# KSP8_Power_Supply_Board_v48.net
KiCad netlist of a schematic drawn in EAGLE
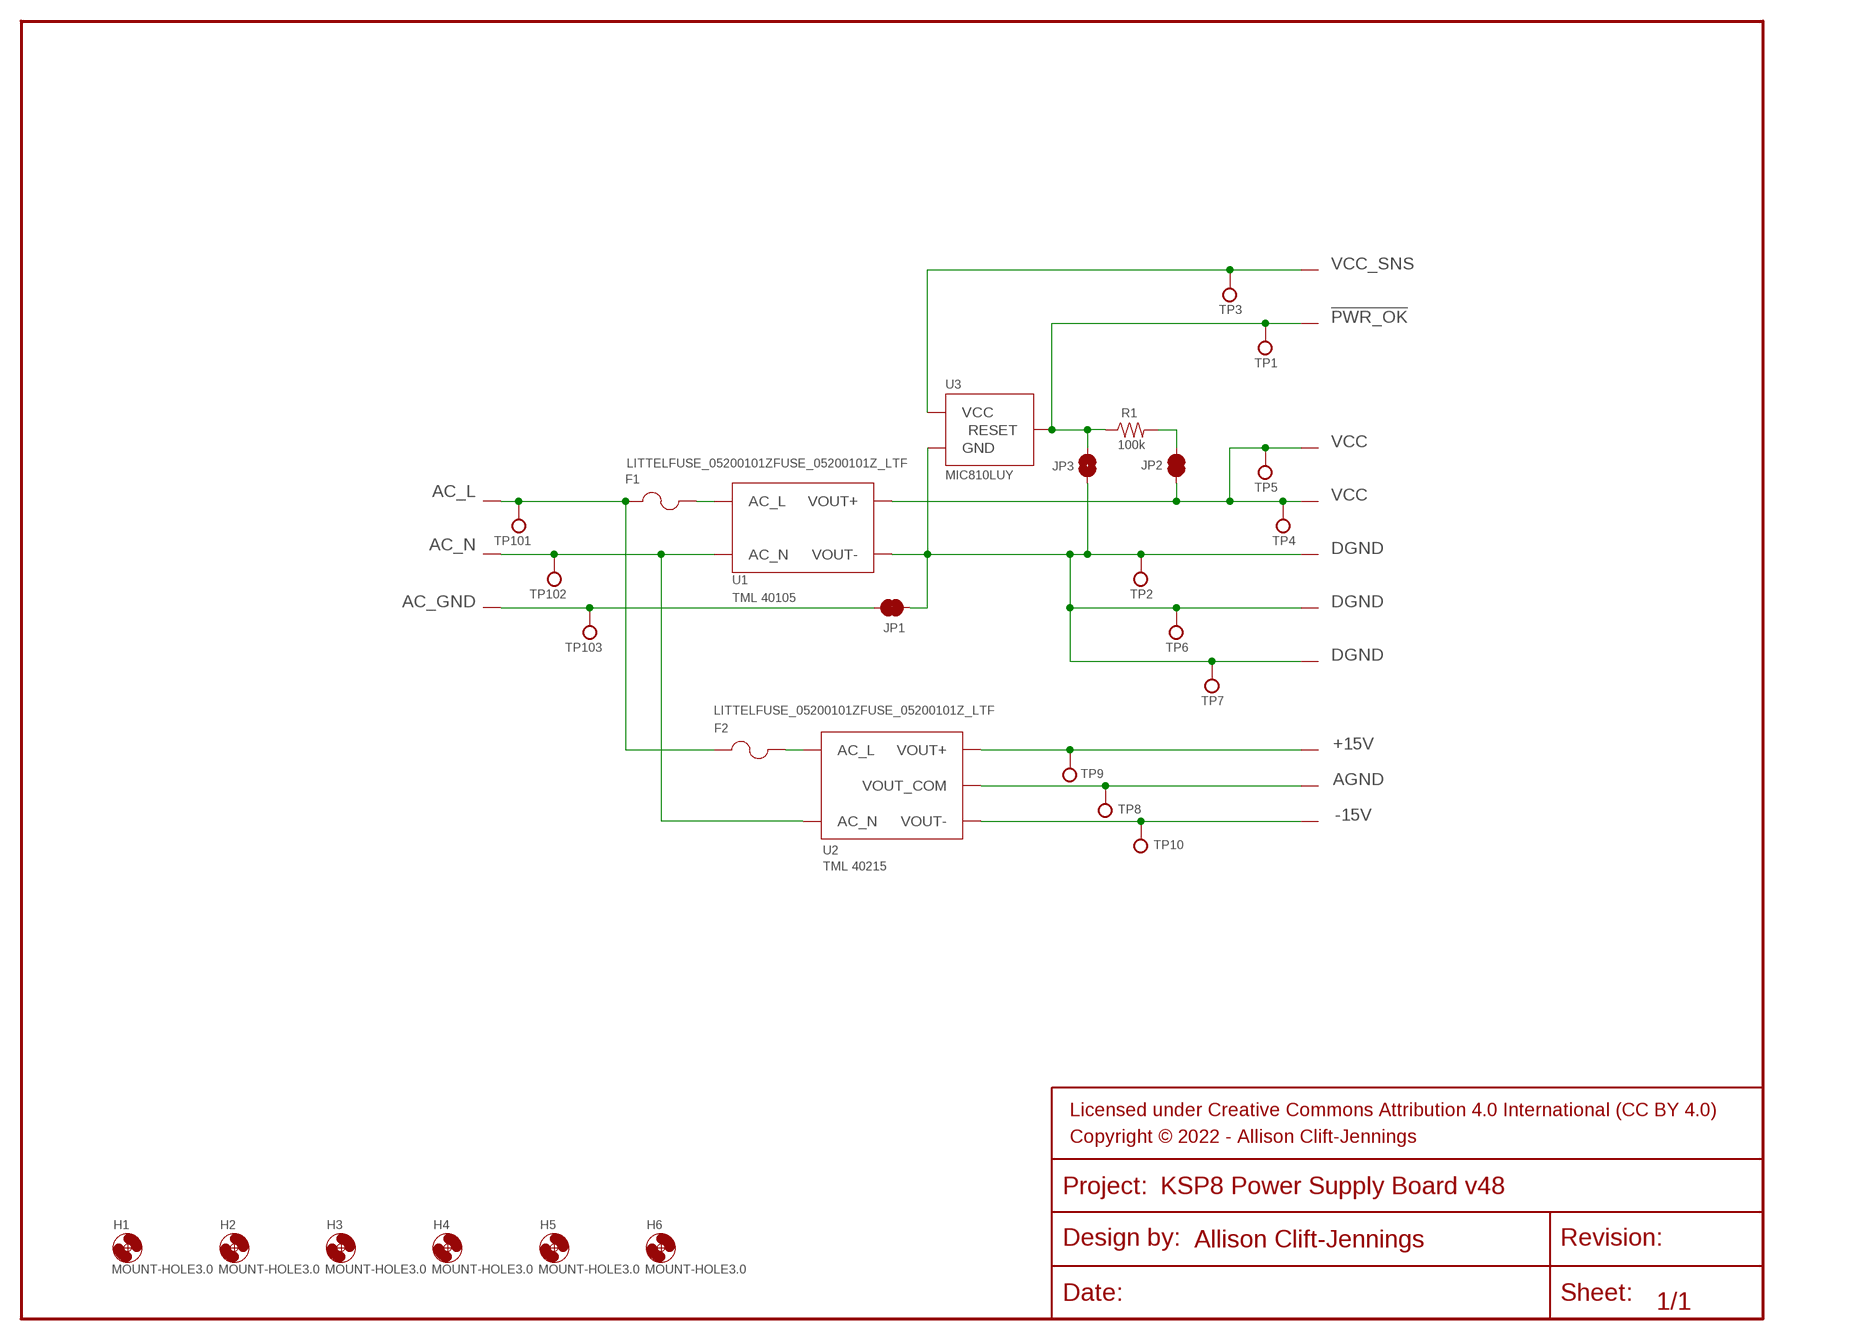
[diagram p0: schematic, sheet 1]

(export (version "E")
  (design (tool "Eeschema 10.0.6"))
  (components
    (comp (ref "AGND")
      (value "PADPAD-070-LOOP")
      (footprint "eagle-import:PAD-067-LOOP")
      (libsource (lib "eagle-import") (part "PAD067-LOOP"))
    )
    (comp (ref "F1")
      (value "LITTELFUSE_05200101ZFUSE_05200101Z_LTF")
      (footprint "eagle-import:LITTELFUSE_05200101Z_LTF")
      (fields
        (field (name "MANUFACTURER_PART_NUMBER") "05200101Z")
        (field (name "COPYRIGHT") "Copyright (C) 2022 Ultra Librarian. All rights reserved.")
      )
      (libsource (lib "eagle-import") (part "LITTELFUSE_05200101ZFUSE_05200101Z_LTF"))
    )
    (comp (ref "F2")
      (value "LITTELFUSE_05200101ZFUSE_05200101Z_LTF")
      (footprint "eagle-import:LITTELFUSE_05200101Z_LTF")
      (fields
        (field (name "MANUFACTURER_PART_NUMBER") "05200101Z")
        (field (name "COPYRIGHT") "Copyright (C) 2022 Ultra Librarian. All rights reserved.")
      )
      (libsource (lib "eagle-import") (part "LITTELFUSE_05200101ZFUSE_05200101Z_LTF"))
    )
    (comp (ref "FRAME1")
      (value "FRAME-LETTER-OS")
      (footprint "eagle-import:CREATIVE_COMMONS")
      (libsource (lib "eagle-import") (part "FRAME-LETTER-OS"))
    )
    (comp (ref "H1")
      (value "MOUNT-HOLE3.0")
      (footprint "eagle-import:3,0")
      (libsource (lib "eagle-import") (part "MOUNT-HOLE3.0"))
    )
    (comp (ref "H2")
      (value "MOUNT-HOLE3.0")
      (footprint "eagle-import:3,0")
      (libsource (lib "eagle-import") (part "MOUNT-HOLE3.0"))
    )
    (comp (ref "H3")
      (value "MOUNT-HOLE3.0")
      (footprint "eagle-import:3,0")
      (libsource (lib "eagle-import") (part "MOUNT-HOLE3.0"))
    )
    (comp (ref "H4")
      (value "MOUNT-HOLE3.0")
      (footprint "eagle-import:3,0")
      (libsource (lib "eagle-import") (part "MOUNT-HOLE3.0"))
    )
    (comp (ref "H5")
      (value "MOUNT-HOLE3.0")
      (footprint "eagle-import:3,0")
      (libsource (lib "eagle-import") (part "MOUNT-HOLE3.0"))
    )
    (comp (ref "H6")
      (value "MOUNT-HOLE3.0")
      (footprint "eagle-import:3,0")
      (libsource (lib "eagle-import") (part "MOUNT-HOLE3.0"))
    )
    (comp (ref "JP1")
      (value "JUMPER-SMT_2_NO_SILK")
      (footprint "eagle-import:SMT-JUMPER_2_NC_TRACE_SILK_HC")
      (libsource (lib "eagle-import") (part "JUMPER-SMT_2_NC_TRACEHC"))
    )
    (comp (ref "JP2")
      (value "JUMPER-SMT_2_NC_TRACE_SILK")
      (footprint "eagle-import:SMT-JUMPER_2_NC_TRACE_SILK")
      (libsource (lib "eagle-import") (part "JUMPER-SMT_2_NC_TRACE_SILK"))
    )
    (comp (ref "JP3")
      (value "JUMPER-SMT_2_NO_SILK")
      (footprint "eagle-import:SMT-JUMPER_2_NO_SILK")
      (libsource (lib "eagle-import") (part "JUMPER-SMT_2_NO_SILK"))
    )
    (comp (ref "R1")
      (value "100k")
      (footprint "eagle-import:1206")
      (libsource (lib "eagle-import") (part "RESISTOR1206"))
    )
    (comp (ref "TP1")
      (value "TESTPOINT")
      (footprint "eagle-import:PAD-100-RND")
      (libsource (lib "eagle-import") (part "TESTPOINT"))
    )
    (comp (ref "TP2")
      (value "TESTPOINT")
      (footprint "eagle-import:PAD-100-RND")
      (libsource (lib "eagle-import") (part "TESTPOINT"))
    )
    (comp (ref "TP3")
      (value "TESTPOINT")
      (footprint "eagle-import:PAD-100-RND")
      (libsource (lib "eagle-import") (part "TESTPOINT"))
    )
    (comp (ref "TP4")
      (value "TESTPOINT")
      (footprint "eagle-import:PAD-100-RND")
      (libsource (lib "eagle-import") (part "TESTPOINT"))
    )
    (comp (ref "TP5")
      (value "TESTPOINT")
      (footprint "eagle-import:PAD-100-RND")
      (libsource (lib "eagle-import") (part "TESTPOINT"))
    )
    (comp (ref "TP6")
      (value "TESTPOINT")
      (footprint "eagle-import:PAD-100-RND")
      (libsource (lib "eagle-import") (part "TESTPOINT"))
    )
    (comp (ref "TP7")
      (value "TESTPOINT")
      (footprint "eagle-import:PAD-100-RND")
      (libsource (lib "eagle-import") (part "TESTPOINT"))
    )
    (comp (ref "TP8")
      (value "TESTPOINT")
      (footprint "eagle-import:PAD-100-RND")
      (libsource (lib "eagle-import") (part "TESTPOINT"))
    )
    (comp (ref "TP9")
      (value "TESTPOINT")
      (footprint "eagle-import:PAD-100-RND")
      (libsource (lib "eagle-import") (part "TESTPOINT"))
    )
    (comp (ref "TP10")
      (value "TESTPOINT")
      (footprint "eagle-import:PAD-100-RND")
      (libsource (lib "eagle-import") (part "TESTPOINT"))
    )
    (comp (ref "TP101")
      (value "TESTPOINT")
      (footprint "eagle-import:PAD-100-RND")
      (libsource (lib "eagle-import") (part "TESTPOINT"))
    )
    (comp (ref "TP102")
      (value "TESTPOINT")
      (footprint "eagle-import:PAD-100-RND")
      (libsource (lib "eagle-import") (part "TESTPOINT"))
    )
    (comp (ref "TP103")
      (value "TESTPOINT")
      (footprint "eagle-import:PAD-100-RND")
      (libsource (lib "eagle-import") (part "TESTPOINT"))
    )
    (comp (ref "U$4")
      (value "PADPAD-070-LOOP")
      (footprint "eagle-import:PAD-067-LOOP")
      (libsource (lib "eagle-import") (part "PAD067-LOOP"))
    )
    (comp (ref "U$5")
      (value "PADPAD-070-LOOP")
      (footprint "eagle-import:PAD-067-LOOP")
      (libsource (lib "eagle-import") (part "PAD067-LOOP"))
    )
    (comp (ref "U$6")
      (value "PADPAD-070-LOOP")
      (footprint "eagle-import:PAD-067-LOOP")
      (libsource (lib "eagle-import") (part "PAD067-LOOP"))
    )
    (comp (ref "U$7")
      (value "PADPAD-070-LOOP")
      (footprint "eagle-import:PAD-067-LOOP")
      (libsource (lib "eagle-import") (part "PAD067-LOOP"))
    )
    (comp (ref "U$8")
      (value "PADPAD-070-LOOP")
      (footprint "eagle-import:PAD-067-LOOP")
      (libsource (lib "eagle-import") (part "PAD067-LOOP"))
    )
    (comp (ref "U$9")
      (value "PADPAD-070-LOOP")
      (footprint "eagle-import:PAD-067-LOOP")
      (libsource (lib "eagle-import") (part "PAD067-LOOP"))
    )
    (comp (ref "U$10")
      (value "PADPAD-070-LOOP")
      (footprint "eagle-import:PAD-067-LOOP")
      (libsource (lib "eagle-import") (part "PAD067-LOOP"))
    )
    (comp (ref "U$11")
      (value "PADPAD-070-LOOP")
      (footprint "eagle-import:PAD-067-LOOP")
      (libsource (lib "eagle-import") (part "PAD067-LOOP"))
    )
    (comp (ref "U$12")
      (value "PADPAD-070-LOOP")
      (footprint "eagle-import:PAD-067-LOOP")
      (libsource (lib "eagle-import") (part "PAD067-LOOP"))
    )
    (comp (ref "U$13")
      (value "PADPAD-070-LOOP")
      (footprint "eagle-import:PAD-067-LOOP")
      (libsource (lib "eagle-import") (part "PAD067-LOOP"))
    )
    (comp (ref "U$14")
      (value "PADPAD-070-LOOP")
      (footprint "eagle-import:PAD-067-LOOP")
      (libsource (lib "eagle-import") (part "PAD067-LOOP"))
    )
    (comp (ref "U$15")
      (value "PADPAD-070-LOOP")
      (footprint "eagle-import:PAD-067-LOOP")
      (libsource (lib "eagle-import") (part "PAD067-LOOP"))
    )
    (comp (ref "U1")
      (value "TML 40105")
      (footprint "eagle-import:TRACO_TML")
      (libsource (lib "eagle-import") (part "TRACO_TML_40105"))
    )
    (comp (ref "U2")
      (value "TML 40215")
      (footprint "eagle-import:TRACO_TML")
      (libsource (lib "eagle-import") (part "TRACO_TML_40215"))
    )
    (comp (ref "U3")
      (value "MIC810LUY")
      (footprint "eagle-import:SOT23")
      (libsource (lib "eagle-import") (part "MIC810"))
    )
  )
  (nets
    (net (code "1") (name "/+15V") (class "Default")
      (node (ref "TP9") (pin "P$1") (pinfunction "P$1_P$1") (pintype "bidirectional"))
      (node (ref "U$6") (pin "P$1") (pinfunction "P$1_P$1") (pintype "bidirectional"))
      (node (ref "U2") (pin "P$4") (pinfunction "VOUT+_P$4") (pintype "power_in"))
    )
    (net (code "2") (name "/-15V") (class "Default")
      (node (ref "TP10") (pin "P$1") (pinfunction "P$1_P$1") (pintype "bidirectional"))
      (node (ref "U$7") (pin "P$1") (pinfunction "P$1_P$1") (pintype "bidirectional"))
      (node (ref "U2") (pin "P$8") (pinfunction "VOUT-_P$8") (pintype "power_in"))
    )
    (net (code "3") (name "/AC_GND") (class "Default")
      (node (ref "JP1") (pin "1") (pinfunction "1_1") (pintype "passive"))
      (node (ref "TP103") (pin "P$1") (pinfunction "P$1_P$1") (pintype "bidirectional"))
      (node (ref "U$11") (pin "P$1") (pinfunction "P$1_P$1") (pintype "bidirectional"))
    )
    (net (code "4") (name "/AC_L") (class "Default")
      (node (ref "F1") (pin "1") (pinfunction "1_1") (pintype "passive"))
      (node (ref "F2") (pin "1") (pinfunction "1_1") (pintype "passive"))
      (node (ref "TP101") (pin "P$1") (pinfunction "P$1_P$1") (pintype "bidirectional"))
      (node (ref "U$4") (pin "P$1") (pinfunction "P$1_P$1") (pintype "bidirectional"))
    )
    (net (code "5") (name "/AC_N") (class "Default")
      (node (ref "TP102") (pin "P$1") (pinfunction "P$1_P$1") (pintype "bidirectional"))
      (node (ref "U$5") (pin "P$1") (pinfunction "P$1_P$1") (pintype "bidirectional"))
      (node (ref "U1") (pin "P$3") (pinfunction "AC_N_P$3") (pintype "power_in"))
      (node (ref "U2") (pin "P$3") (pinfunction "AC_N_P$3") (pintype "power_in"))
    )
    (net (code "6") (name "/AGND") (class "Default")
      (node (ref "AGND") (pin "P$1") (pinfunction "P$1_P$1") (pintype "bidirectional"))
      (node (ref "TP8") (pin "P$1") (pinfunction "P$1_P$1") (pintype "bidirectional"))
      (node (ref "U2") (pin "P$6") (pinfunction "VOUT_COM_P$6") (pintype "power_in"))
    )
    (net (code "7") (name "/DGND") (class "Default")
      (node (ref "JP1") (pin "2") (pinfunction "2_2") (pintype "passive"))
      (node (ref "JP3") (pin "1") (pinfunction "1_1") (pintype "passive"))
      (node (ref "TP2") (pin "P$1") (pinfunction "P$1_P$1") (pintype "bidirectional"))
      (node (ref "TP6") (pin "P$1") (pinfunction "P$1_P$1") (pintype "bidirectional"))
      (node (ref "TP7") (pin "P$1") (pinfunction "P$1_P$1") (pintype "bidirectional"))
      (node (ref "U$10") (pin "P$1") (pinfunction "P$1_P$1") (pintype "bidirectional"))
      (node (ref "U$13") (pin "P$1") (pinfunction "P$1_P$1") (pintype "bidirectional"))
      (node (ref "U$14") (pin "P$1") (pinfunction "P$1_P$1") (pintype "bidirectional"))
      (node (ref "U1") (pin "P$6") (pinfunction "VOUT-_P$6") (pintype "bidirectional"))
      (node (ref "U3") (pin "1") (pinfunction "GND_1") (pintype "power_in"))
    )
    (net (code "8") (name "/VCC") (class "Default")
      (node (ref "JP2") (pin "2") (pinfunction "2_2") (pintype "passive"))
      (node (ref "TP4") (pin "P$1") (pinfunction "P$1_P$1") (pintype "bidirectional"))
      (node (ref "TP5") (pin "P$1") (pinfunction "P$1_P$1") (pintype "bidirectional"))
      (node (ref "U$15") (pin "P$1") (pinfunction "P$1_P$1") (pintype "bidirectional"))
      (node (ref "U$9") (pin "P$1") (pinfunction "P$1_P$1") (pintype "bidirectional"))
      (node (ref "U1") (pin "P$4") (pinfunction "VOUT+_P$4") (pintype "power_in"))
    )
    (net (code "9") (name "/VCC_SNS") (class "Default")
      (node (ref "TP3") (pin "P$1") (pinfunction "P$1_P$1") (pintype "bidirectional"))
      (node (ref "U$12") (pin "P$1") (pinfunction "P$1_P$1") (pintype "bidirectional"))
      (node (ref "U3") (pin "3") (pinfunction "VCC_3") (pintype "power_in"))
    )
    (net (code "10") (name "/~{PWR_OK}") (class "Default")
      (node (ref "JP3") (pin "2") (pinfunction "2_2") (pintype "passive"))
      (node (ref "R1") (pin "1") (pinfunction "1_1") (pintype "passive"))
      (node (ref "TP1") (pin "P$1") (pinfunction "P$1_P$1") (pintype "bidirectional"))
      (node (ref "U$8") (pin "P$1") (pinfunction "P$1_P$1") (pintype "bidirectional"))
      (node (ref "U3") (pin "2") (pinfunction "RESET_2") (pintype "output"))
    )
    (net (code "11") (name "Net-(JP2-Pad1)") (class "Default")
      (node (ref "JP2") (pin "1") (pinfunction "1_1") (pintype "passive"))
      (node (ref "R1") (pin "2") (pinfunction "2_2") (pintype "passive"))
    )
    (net (code "12") (name "Net-(U1-AC_L)") (class "Default")
      (node (ref "F1") (pin "2") (pinfunction "2_2") (pintype "passive"))
      (node (ref "U1") (pin "P$2") (pinfunction "AC_L_P$2") (pintype "power_in"))
    )
    (net (code "13") (name "Net-(U2-AC_L)") (class "Default")
      (node (ref "F2") (pin "2") (pinfunction "2_2") (pintype "passive"))
      (node (ref "U2") (pin "P$2") (pinfunction "AC_L_P$2") (pintype "power_in"))
    )
  )
)
